# SIDE.net
KiCad netlist of a schematic drawn in Altium Designer
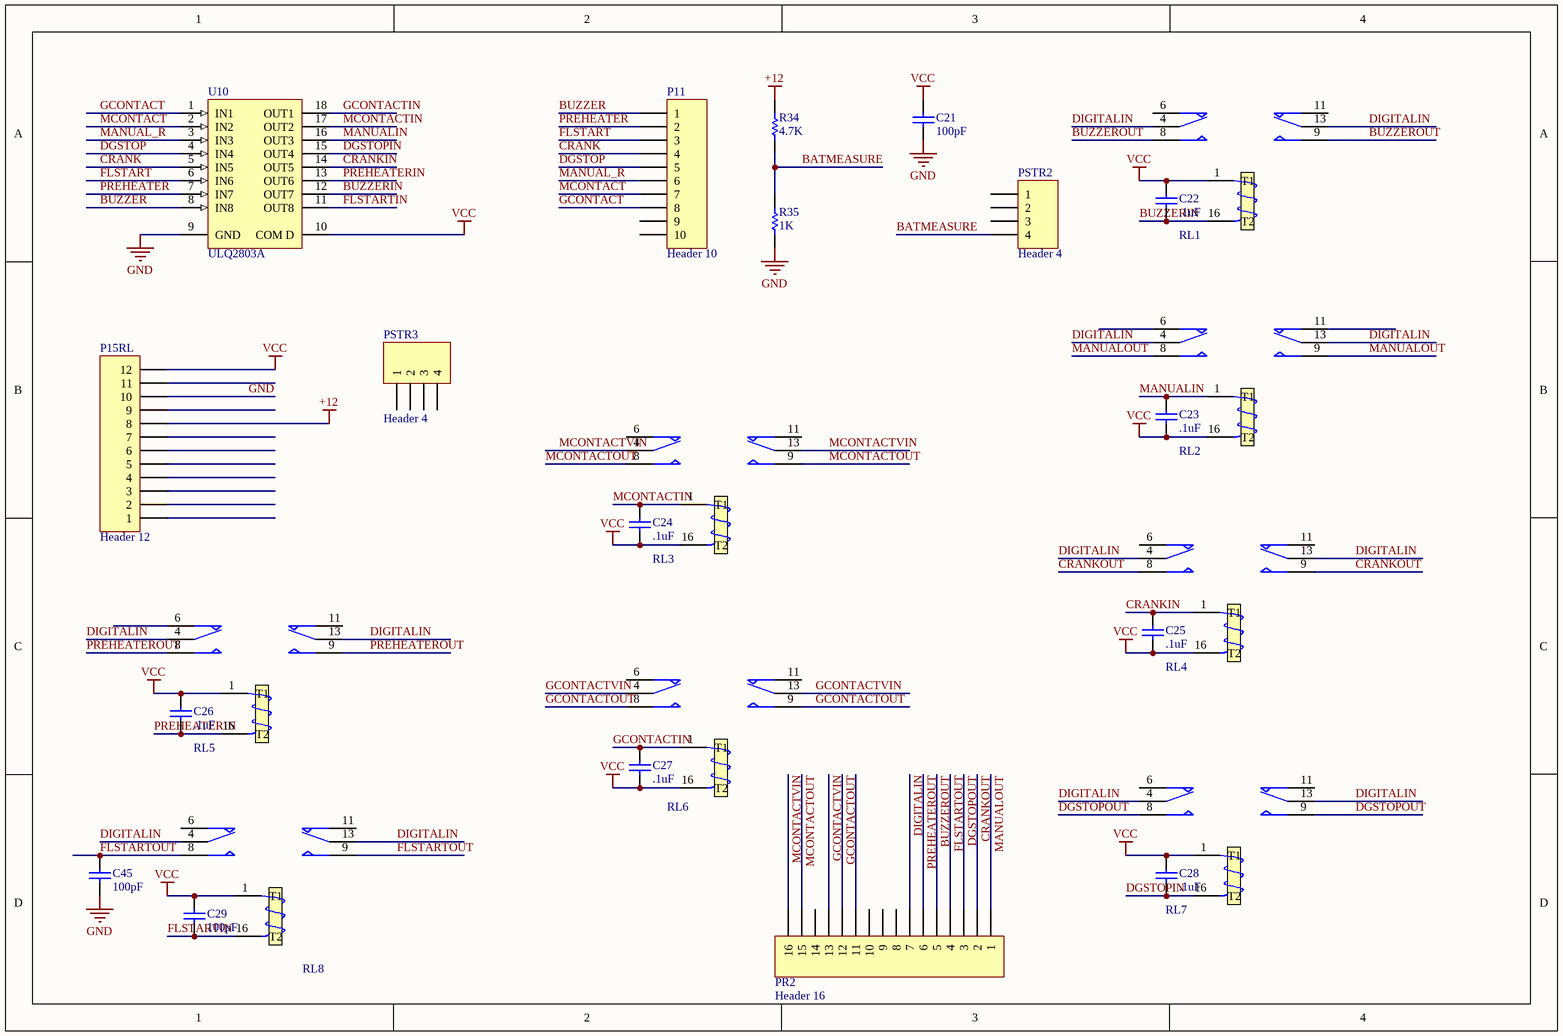
[diagram p0: SIDE.SchDoc]

(export (version "E")
  (design (tool "Eeschema 10.0.6"))
  (components
    (comp (ref "C21")
      (value "100pF")
      (footprint "RAD-0.2")
      (description "Capacitor")
      (fields (field (name "Comment") "Cap Ceramic .1uF") (field (name "PUBLISHER") "Altium Limited"))
      (libsource (lib "Miscellaneous Devices") (part "Cap"))
    )
    (comp (ref "C22")
      (value ".1uF")
      (description "Capacitor")
      (fields (field (name "Comment") "CAP") (field (name "PUBLISHER") "Altium Limited"))
      (libsource (lib "Miscellaneous Devices") (part "Cap"))
    )
    (comp (ref "C23")
      (value ".1uF")
      (description "Capacitor")
      (fields (field (name "Comment") "CAP") (field (name "PUBLISHER") "Altium Limited"))
      (libsource (lib "Miscellaneous Devices") (part "Cap"))
    )
    (comp (ref "C24")
      (value ".1uF")
      (description "Capacitor")
      (fields (field (name "Comment") "CAP") (field (name "PUBLISHER") "Altium Limited"))
      (libsource (lib "Miscellaneous Devices") (part "Cap"))
    )
    (comp (ref "C25")
      (value ".1uF")
      (description "Capacitor")
      (fields (field (name "Comment") "CAP") (field (name "PUBLISHER") "Altium Limited"))
      (libsource (lib "Miscellaneous Devices") (part "Cap"))
    )
    (comp (ref "C26")
      (value ".1uF")
      (description "Capacitor")
      (fields (field (name "Comment") "CAP") (field (name "PUBLISHER") "Altium Limited"))
      (libsource (lib "Miscellaneous Devices") (part "Cap"))
    )
    (comp (ref "C27")
      (value ".1uF")
      (description "Capacitor")
      (fields (field (name "Comment") "CAP") (field (name "PUBLISHER") "Altium Limited"))
      (libsource (lib "Miscellaneous Devices") (part "Cap"))
    )
    (comp (ref "C28")
      (value ".1uF")
      (description "Capacitor")
      (fields (field (name "Comment") "CAP") (field (name "PUBLISHER") "Altium Limited"))
      (libsource (lib "Miscellaneous Devices") (part "Cap"))
    )
    (comp (ref "C29")
      (value "100pF")
      (footprint "RAD-0.2")
      (description "Capacitor")
      (fields (field (name "Comment") "CAP") (field (name "PUBLISHER") "Altium Limited"))
      (libsource (lib "Miscellaneous Devices") (part "Cap"))
    )
    (comp (ref "C45")
      (value "100pF")
      (footprint "RAD-0.2")
      (description "Capacitor")
      (fields (field (name "Comment") "CAP") (field (name "PUBLISHER") "Altium Limited"))
      (libsource (lib "Miscellaneous Devices") (part "Cap"))
    )
    (comp (ref "P11")
      (value "Header 10")
      (footprint "HDR1X10")
      (description "Header, 10-Pin")
      (fields (field (name "PUBLISHER") "Altium Limited"))
      (libsource (lib "Miscellaneous Connectors") (part "Header 10"))
    )
    (comp (ref "P15RL")
      (value "Header 12")
      (footprint "HDR1X12")
      (description "Header, 12-Pin")
      (fields (field (name "PUBLISHER") "Altium Limited"))
      (libsource (lib "Miscellaneous Connectors") (part "Header 12"))
    )
    (comp (ref "PR2")
      (value "Header 16")
      (footprint "HDR1X16")
      (description "Header, 16-Pin")
      (fields (field (name "PUBLISHER") "Altium Limited"))
      (libsource (lib "Miscellaneous Connectors") (part "Header 16"))
    )
    (comp (ref "PSTR2")
      (value "Header 4")
      (footprint "HDR1X4")
      (description "Header, 4-Pin")
      (fields (field (name "PUBLISHER") "Altium Limited"))
      (libsource (lib "") (part "Header 4_1"))
    )
    (comp (ref "PSTR3")
      (value "Header 4")
      (footprint "HDR1X4")
      (description "Header, 4-Pin")
      (fields (field (name "PUBLISHER") "Altium Limited"))
      (libsource (lib "Miscellaneous Connectors") (part "Header 4"))
    )
    (comp (ref "R34")
      (value "4.7K")
      (footprint "AXIAL-0.4")
      (description "Resistor")
      (fields (field (name "Comment") "Res 4.7K") (field (name "PUBLISHER") "Altium Limited"))
      (libsource (lib "Miscellaneous Devices") (part "Res1"))
    )
    (comp (ref "R35")
      (value "1K")
      (footprint "AXIAL-0.4")
      (description "Resistor")
      (fields (field (name "Comment") "Res 1K") (field (name "PUBLISHER") "Altium Limited"))
      (libsource (lib "Miscellaneous Devices") (part "Res1"))
    )
    (comp (ref "RL1")
      (value "DPDT RELAY")
      (footprint "RELAYDPDT")
      (libsource (lib "PCB_Project1") (part "RELAYDPDT"))
    )
    (comp (ref "RL2")
      (value "DPDT RELAY")
      (footprint "RELAYDPDT")
      (libsource (lib "PCB_Project1") (part "RELAYDPDT"))
    )
    (comp (ref "RL3")
      (value "DPDT RELAY")
      (footprint "RELAYDPDT")
      (libsource (lib "PCB_Project1") (part "RELAYDPDT"))
    )
    (comp (ref "RL4")
      (value "DPDT RELAY")
      (footprint "RELAYDPDT")
      (libsource (lib "PCB_Project1") (part "RELAYDPDT"))
    )
    (comp (ref "RL5")
      (value "DPDT RELAY")
      (footprint "RELAYDPDT")
      (libsource (lib "PCB_Project1") (part "RELAYDPDT"))
    )
    (comp (ref "RL6")
      (value "DPDT RELAY")
      (footprint "RELAYDPDT")
      (libsource (lib "PCB_Project1") (part "RELAYDPDT"))
    )
    (comp (ref "RL7")
      (value "DPDT RELAY")
      (footprint "RELAYDPDT")
      (libsource (lib "PCB_Project1") (part "RELAYDPDT"))
    )
    (comp (ref "RL8")
      (value "DPDT RELAY")
      (footprint "RELAYDPDT")
      (libsource (lib "PCB_Project1") (part "RELAYDPDT"))
    )
    (comp (ref "U10")
      (value "ULQ2803A")
      (footprint "DIP18")
      (description "Eight Darlington Array")
      (fields (field (name "PUBLISHER") "Altium Limited"))
      (libsource (lib "ST Interface Darlington Driver") (part "ULQ2803A"))
    )
  )
  (nets
    (net (code "1") (name "+12") (class "Default")
      (node (ref "P15RL") (pin "8") (pinfunction "8_8") (pintype "passive"))
      (node (ref "R34") (pin "2") (pinfunction "2_2") (pintype "passive"))
    )
    (net (code "2") (name "/BATMEASURE") (class "Default")
      (node (ref "PSTR2") (pin "4") (pinfunction "4_4") (pintype "passive"))
      (node (ref "R34") (pin "1") (pinfunction "1_1") (pintype "passive"))
      (node (ref "R35") (pin "2") (pinfunction "2_2") (pintype "passive"))
    )
    (net (code "3") (name "/BUZZER") (class "Default")
      (node (ref "P11") (pin "1") (pinfunction "1_1") (pintype "passive"))
      (node (ref "U10") (pin "8") (pinfunction "IN8_8") (pintype "input"))
    )
    (net (code "4") (name "/BUZZERIN") (class "Default")
      (node (ref "C22") (pin "1") (pinfunction "1_1") (pintype "passive"))
      (node (ref "RL1") (pin "16") (pinfunction "T2_16") (pintype "passive"))
      (node (ref "U10") (pin "12") (pinfunction "OUT7_12") (pintype "open_collector"))
    )
    (net (code "5") (name "/BUZZEROUT") (class "Default")
      (node (ref "PR2") (pin "5") (pinfunction "5_5") (pintype "passive"))
      (node (ref "RL1") (pin "8") (pinfunction "NO_8") (pintype "passive"))
      (node (ref "RL1") (pin "9") (pinfunction "NO_9") (pintype "passive"))
    )
    (net (code "6") (name "/CRANK") (class "Default")
      (node (ref "P11") (pin "4") (pinfunction "4_4") (pintype "passive"))
      (node (ref "U10") (pin "5") (pinfunction "IN5_5") (pintype "input"))
    )
    (net (code "7") (name "/CRANKIN") (class "Default")
      (node (ref "C25") (pin "2") (pinfunction "2_2") (pintype "passive"))
      (node (ref "RL4") (pin "1") (pinfunction "T1_1") (pintype "passive"))
      (node (ref "U10") (pin "14") (pinfunction "OUT5_14") (pintype "open_collector"))
    )
    (net (code "8") (name "/CRANKOUT") (class "Default")
      (node (ref "PR2") (pin "2") (pinfunction "2_2") (pintype "passive"))
      (node (ref "RL4") (pin "8") (pinfunction "NO_8") (pintype "passive"))
      (node (ref "RL4") (pin "9") (pinfunction "NO_9") (pintype "passive"))
    )
    (net (code "9") (name "/DGSTOP") (class "Default")
      (node (ref "P11") (pin "5") (pinfunction "5_5") (pintype "passive"))
      (node (ref "U10") (pin "4") (pinfunction "IN4_4") (pintype "input"))
    )
    (net (code "10") (name "/DGSTOPIN") (class "Default")
      (node (ref "C28") (pin "1") (pinfunction "1_1") (pintype "passive"))
      (node (ref "RL7") (pin "16") (pinfunction "T2_16") (pintype "passive"))
      (node (ref "U10") (pin "15") (pinfunction "OUT4_15") (pintype "open_collector"))
    )
    (net (code "11") (name "/DGSTOPOUT") (class "Default")
      (node (ref "PR2") (pin "3") (pinfunction "3_3") (pintype "passive"))
      (node (ref "RL7") (pin "8") (pinfunction "NO_8") (pintype "passive"))
      (node (ref "RL7") (pin "9") (pinfunction "NO_9") (pintype "passive"))
    )
    (net (code "12") (name "/DIGITALIN") (class "Default")
      (node (ref "PR2") (pin "7") (pinfunction "7_7") (pintype "passive"))
      (node (ref "RL1") (pin "13") (pinfunction "COM_13") (pintype "passive"))
      (node (ref "RL1") (pin "4") (pinfunction "COM_4") (pintype "passive"))
      (node (ref "RL2") (pin "13") (pinfunction "COM_13") (pintype "passive"))
      (node (ref "RL2") (pin "4") (pinfunction "COM_4") (pintype "passive"))
      (node (ref "RL4") (pin "13") (pinfunction "COM_13") (pintype "passive"))
      (node (ref "RL4") (pin "4") (pinfunction "COM_4") (pintype "passive"))
      (node (ref "RL5") (pin "13") (pinfunction "COM_13") (pintype "passive"))
      (node (ref "RL5") (pin "4") (pinfunction "COM_4") (pintype "passive"))
      (node (ref "RL7") (pin "13") (pinfunction "COM_13") (pintype "passive"))
      (node (ref "RL7") (pin "4") (pinfunction "COM_4") (pintype "passive"))
      (node (ref "RL8") (pin "13") (pinfunction "COM_13") (pintype "passive"))
      (node (ref "RL8") (pin "4") (pinfunction "COM_4") (pintype "passive"))
    )
    (net (code "13") (name "/FLSTART") (class "Default")
      (node (ref "P11") (pin "3") (pinfunction "3_3") (pintype "passive"))
      (node (ref "U10") (pin "6") (pinfunction "IN6_6") (pintype "input"))
    )
    (net (code "14") (name "/FLSTARTIN") (class "Default")
      (node (ref "C29") (pin "1") (pinfunction "1_1") (pintype "passive"))
      (node (ref "RL8") (pin "16") (pinfunction "T2_16") (pintype "passive"))
      (node (ref "U10") (pin "11") (pinfunction "OUT8_11") (pintype "open_collector"))
    )
    (net (code "15") (name "/FLSTARTOUT") (class "Default")
      (node (ref "C45") (pin "2") (pinfunction "2_2") (pintype "passive"))
      (node (ref "PR2") (pin "4") (pinfunction "4_4") (pintype "passive"))
      (node (ref "RL8") (pin "8") (pinfunction "NO_8") (pintype "passive"))
      (node (ref "RL8") (pin "9") (pinfunction "NO_9") (pintype "passive"))
    )
    (net (code "16") (name "/GCONTACT") (class "Default")
      (node (ref "P11") (pin "8") (pinfunction "8_8") (pintype "passive"))
      (node (ref "U10") (pin "1") (pinfunction "IN1_1") (pintype "input"))
    )
    (net (code "17") (name "/GCONTACTIN") (class "Default")
      (node (ref "C27") (pin "2") (pinfunction "2_2") (pintype "passive"))
      (node (ref "RL6") (pin "1") (pinfunction "T1_1") (pintype "passive"))
      (node (ref "U10") (pin "18") (pinfunction "OUT1_18") (pintype "open_collector"))
    )
    (net (code "18") (name "/GCONTACTOUT") (class "Default")
      (node (ref "PR2") (pin "12") (pinfunction "12_12") (pintype "passive"))
      (node (ref "RL6") (pin "8") (pinfunction "NO_8") (pintype "passive"))
      (node (ref "RL6") (pin "9") (pinfunction "NO_9") (pintype "passive"))
    )
    (net (code "19") (name "/GCONTACTVIN") (class "Default")
      (node (ref "PR2") (pin "13") (pinfunction "13_13") (pintype "passive"))
      (node (ref "RL6") (pin "13") (pinfunction "COM_13") (pintype "passive"))
      (node (ref "RL6") (pin "4") (pinfunction "COM_4") (pintype "passive"))
    )
    (net (code "20") (name "/MANUALIN") (class "Default")
      (node (ref "C23") (pin "2") (pinfunction "2_2") (pintype "passive"))
      (node (ref "RL2") (pin "1") (pinfunction "T1_1") (pintype "passive"))
      (node (ref "U10") (pin "16") (pinfunction "OUT3_16") (pintype "open_collector"))
    )
    (net (code "21") (name "/MANUALOUT") (class "Default")
      (node (ref "PR2") (pin "1") (pinfunction "1_1") (pintype "passive"))
      (node (ref "RL2") (pin "8") (pinfunction "NO_8") (pintype "passive"))
      (node (ref "RL2") (pin "9") (pinfunction "NO_9") (pintype "passive"))
    )
    (net (code "22") (name "/MANUAL_R") (class "Default")
      (node (ref "P11") (pin "6") (pinfunction "6_6") (pintype "passive"))
      (node (ref "U10") (pin "3") (pinfunction "IN3_3") (pintype "input"))
    )
    (net (code "23") (name "/MCONTACT") (class "Default")
      (node (ref "P11") (pin "7") (pinfunction "7_7") (pintype "passive"))
      (node (ref "U10") (pin "2") (pinfunction "IN2_2") (pintype "input"))
    )
    (net (code "24") (name "/MCONTACTIN") (class "Default")
      (node (ref "C24") (pin "2") (pinfunction "2_2") (pintype "passive"))
      (node (ref "RL3") (pin "1") (pinfunction "T1_1") (pintype "passive"))
      (node (ref "U10") (pin "17") (pinfunction "OUT2_17") (pintype "open_collector"))
    )
    (net (code "25") (name "/MCONTACTOUT") (class "Default")
      (node (ref "PR2") (pin "15") (pinfunction "15_15") (pintype "passive"))
      (node (ref "RL3") (pin "8") (pinfunction "NO_8") (pintype "passive"))
      (node (ref "RL3") (pin "9") (pinfunction "NO_9") (pintype "passive"))
    )
    (net (code "26") (name "/MCONTACTVIN") (class "Default")
      (node (ref "PR2") (pin "16") (pinfunction "16_16") (pintype "passive"))
      (node (ref "RL3") (pin "13") (pinfunction "COM_13") (pintype "passive"))
      (node (ref "RL3") (pin "4") (pinfunction "COM_4") (pintype "passive"))
    )
    (net (code "27") (name "/PREHEATER") (class "Default")
      (node (ref "P11") (pin "2") (pinfunction "2_2") (pintype "passive"))
      (node (ref "U10") (pin "7") (pinfunction "IN7_7") (pintype "input"))
    )
    (net (code "28") (name "/PREHEATERIN") (class "Default")
      (node (ref "C26") (pin "1") (pinfunction "1_1") (pintype "passive"))
      (node (ref "RL5") (pin "16") (pinfunction "T2_16") (pintype "passive"))
      (node (ref "U10") (pin "13") (pinfunction "OUT6_13") (pintype "open_collector"))
    )
    (net (code "29") (name "/PREHEATEROUT") (class "Default")
      (node (ref "PR2") (pin "6") (pinfunction "6_6") (pintype "passive"))
      (node (ref "RL5") (pin "8") (pinfunction "NO_8") (pintype "passive"))
      (node (ref "RL5") (pin "9") (pinfunction "NO_9") (pintype "passive"))
    )
    (net (code "30") (name "GND") (class "Default")
      (node (ref "C21") (pin "1") (pinfunction "1_1") (pintype "passive"))
      (node (ref "C45") (pin "1") (pinfunction "1_1") (pintype "passive"))
      (node (ref "P15RL") (pin "10") (pinfunction "10_10") (pintype "passive"))
      (node (ref "R35") (pin "1") (pinfunction "1_1") (pintype "passive"))
      (node (ref "U10") (pin "9") (pinfunction "GND_9") (pintype "power_in"))
    )
    (net (code "31") (name "VCC") (class "Default")
      (node (ref "C21") (pin "2") (pinfunction "2_2") (pintype "passive"))
      (node (ref "C22") (pin "2") (pinfunction "2_2") (pintype "passive"))
      (node (ref "C23") (pin "1") (pinfunction "1_1") (pintype "passive"))
      (node (ref "C24") (pin "1") (pinfunction "1_1") (pintype "passive"))
      (node (ref "C25") (pin "1") (pinfunction "1_1") (pintype "passive"))
      (node (ref "C26") (pin "2") (pinfunction "2_2") (pintype "passive"))
      (node (ref "C27") (pin "1") (pinfunction "1_1") (pintype "passive"))
      (node (ref "C28") (pin "2") (pinfunction "2_2") (pintype "passive"))
      (node (ref "C29") (pin "2") (pinfunction "2_2") (pintype "passive"))
      (node (ref "P15RL") (pin "12") (pinfunction "12_12") (pintype "passive"))
      (node (ref "RL1") (pin "1") (pinfunction "T1_1") (pintype "passive"))
      (node (ref "RL2") (pin "16") (pinfunction "T2_16") (pintype "passive"))
      (node (ref "RL3") (pin "16") (pinfunction "T2_16") (pintype "passive"))
      (node (ref "RL4") (pin "16") (pinfunction "T2_16") (pintype "passive"))
      (node (ref "RL5") (pin "1") (pinfunction "T1_1") (pintype "passive"))
      (node (ref "RL6") (pin "16") (pinfunction "T2_16") (pintype "passive"))
      (node (ref "RL7") (pin "1") (pinfunction "T1_1") (pintype "passive"))
      (node (ref "RL8") (pin "1") (pinfunction "T1_1") (pintype "passive"))
      (node (ref "U10") (pin "10") (pinfunction "COM_D_10") (pintype "passive"))
    )
    (net (code "32") (name "unconnected-(P11-Pad9)") (class "Default")
      (node (ref "P11") (pin "9") (pinfunction "9_9") (pintype "passive"))
    )
    (net (code "33") (name "unconnected-(P11-Pad10)") (class "Default")
      (node (ref "P11") (pin "10") (pinfunction "10_10") (pintype "passive"))
    )
    (net (code "34") (name "unconnected-(P15RL-Pad1)") (class "Default")
      (node (ref "P15RL") (pin "1") (pinfunction "1_1") (pintype "passive"))
    )
    (net (code "35") (name "unconnected-(P15RL-Pad2)") (class "Default")
      (node (ref "P15RL") (pin "2") (pinfunction "2_2") (pintype "passive"))
    )
    (net (code "36") (name "unconnected-(P15RL-Pad3)") (class "Default")
      (node (ref "P15RL") (pin "3") (pinfunction "3_3") (pintype "passive"))
    )
    (net (code "37") (name "unconnected-(P15RL-Pad4)") (class "Default")
      (node (ref "P15RL") (pin "4") (pinfunction "4_4") (pintype "passive"))
    )
    (net (code "38") (name "unconnected-(P15RL-Pad5)") (class "Default")
      (node (ref "P15RL") (pin "5") (pinfunction "5_5") (pintype "passive"))
    )
    (net (code "39") (name "unconnected-(P15RL-Pad6)") (class "Default")
      (node (ref "P15RL") (pin "6") (pinfunction "6_6") (pintype "passive"))
    )
    (net (code "40") (name "unconnected-(P15RL-Pad7)") (class "Default")
      (node (ref "P15RL") (pin "7") (pinfunction "7_7") (pintype "passive"))
    )
    (net (code "41") (name "unconnected-(P15RL-Pad9)") (class "Default")
      (node (ref "P15RL") (pin "9") (pinfunction "9_9") (pintype "passive"))
    )
    (net (code "42") (name "unconnected-(P15RL-Pad11)") (class "Default")
      (node (ref "P15RL") (pin "11") (pinfunction "11_11") (pintype "passive"))
    )
    (net (code "43") (name "unconnected-(PR2-Pad8)") (class "Default")
      (node (ref "PR2") (pin "8") (pinfunction "8_8") (pintype "passive"))
    )
    (net (code "44") (name "unconnected-(PR2-Pad9)") (class "Default")
      (node (ref "PR2") (pin "9") (pinfunction "9_9") (pintype "passive"))
    )
    (net (code "45") (name "unconnected-(PR2-Pad10)") (class "Default")
      (node (ref "PR2") (pin "10") (pinfunction "10_10") (pintype "passive"))
    )
    (net (code "46") (name "unconnected-(PR2-Pad11)") (class "Default")
      (node (ref "PR2") (pin "11") (pinfunction "11_11") (pintype "passive"))
    )
    (net (code "47") (name "unconnected-(PR2-Pad14)") (class "Default")
      (node (ref "PR2") (pin "14") (pinfunction "14_14") (pintype "passive"))
    )
    (net (code "48") (name "unconnected-(PSTR2-Pad1)") (class "Default")
      (node (ref "PSTR2") (pin "1") (pinfunction "1_1") (pintype "passive"))
    )
    (net (code "49") (name "unconnected-(PSTR2-Pad2)") (class "Default")
      (node (ref "PSTR2") (pin "2") (pinfunction "2_2") (pintype "passive"))
    )
    (net (code "50") (name "unconnected-(PSTR2-Pad3)") (class "Default")
      (node (ref "PSTR2") (pin "3") (pinfunction "3_3") (pintype "passive"))
    )
    (net (code "51") (name "unconnected-(PSTR3-Pad1)") (class "Default")
      (node (ref "PSTR3") (pin "1") (pinfunction "1_1") (pintype "passive"))
    )
    (net (code "52") (name "unconnected-(PSTR3-Pad2)") (class "Default")
      (node (ref "PSTR3") (pin "2") (pinfunction "2_2") (pintype "passive"))
    )
    (net (code "53") (name "unconnected-(PSTR3-Pad3)") (class "Default")
      (node (ref "PSTR3") (pin "3") (pinfunction "3_3") (pintype "passive"))
    )
    (net (code "54") (name "unconnected-(PSTR3-Pad4)") (class "Default")
      (node (ref "PSTR3") (pin "4") (pinfunction "4_4") (pintype "passive"))
    )
    (net (code "55") (name "unconnected-(RL1-NC-Pad6)") (class "Default")
      (node (ref "RL1") (pin "6") (pinfunction "NC_6") (pintype "passive"))
    )
    (net (code "56") (name "unconnected-(RL1-NC-Pad11)") (class "Default")
      (node (ref "RL1") (pin "11") (pinfunction "NC_11") (pintype "passive"))
    )
    (net (code "57") (name "unconnected-(RL2-NC-Pad6)") (class "Default")
      (node (ref "RL2") (pin "6") (pinfunction "NC_6") (pintype "passive"))
    )
    (net (code "58") (name "unconnected-(RL2-NC-Pad11)") (class "Default")
      (node (ref "RL2") (pin "11") (pinfunction "NC_11") (pintype "passive"))
    )
    (net (code "59") (name "unconnected-(RL3-NC-Pad6)") (class "Default")
      (node (ref "RL3") (pin "6") (pinfunction "NC_6") (pintype "passive"))
    )
    (net (code "60") (name "unconnected-(RL3-NC-Pad11)") (class "Default")
      (node (ref "RL3") (pin "11") (pinfunction "NC_11") (pintype "passive"))
    )
    (net (code "61") (name "unconnected-(RL4-NC-Pad6)") (class "Default")
      (node (ref "RL4") (pin "6") (pinfunction "NC_6") (pintype "passive"))
    )
    (net (code "62") (name "unconnected-(RL4-NC-Pad11)") (class "Default")
      (node (ref "RL4") (pin "11") (pinfunction "NC_11") (pintype "passive"))
    )
    (net (code "63") (name "unconnected-(RL5-NC-Pad6)") (class "Default")
      (node (ref "RL5") (pin "6") (pinfunction "NC_6") (pintype "passive"))
    )
    (net (code "64") (name "unconnected-(RL5-NC-Pad11)") (class "Default")
      (node (ref "RL5") (pin "11") (pinfunction "NC_11") (pintype "passive"))
    )
    (net (code "65") (name "unconnected-(RL6-NC-Pad6)") (class "Default")
      (node (ref "RL6") (pin "6") (pinfunction "NC_6") (pintype "passive"))
    )
    (net (code "66") (name "unconnected-(RL6-NC-Pad11)") (class "Default")
      (node (ref "RL6") (pin "11") (pinfunction "NC_11") (pintype "passive"))
    )
    (net (code "67") (name "unconnected-(RL7-NC-Pad6)") (class "Default")
      (node (ref "RL7") (pin "6") (pinfunction "NC_6") (pintype "passive"))
    )
    (net (code "68") (name "unconnected-(RL7-NC-Pad11)") (class "Default")
      (node (ref "RL7") (pin "11") (pinfunction "NC_11") (pintype "passive"))
    )
    (net (code "69") (name "unconnected-(RL8-NC-Pad6)") (class "Default")
      (node (ref "RL8") (pin "6") (pinfunction "NC_6") (pintype "passive"))
    )
    (net (code "70") (name "unconnected-(RL8-NC-Pad11)") (class "Default")
      (node (ref "RL8") (pin "11") (pinfunction "NC_11") (pintype "passive"))
    )
  )
)
